# Micro.net
KiCad netlist of a schematic drawn in Altium Designer
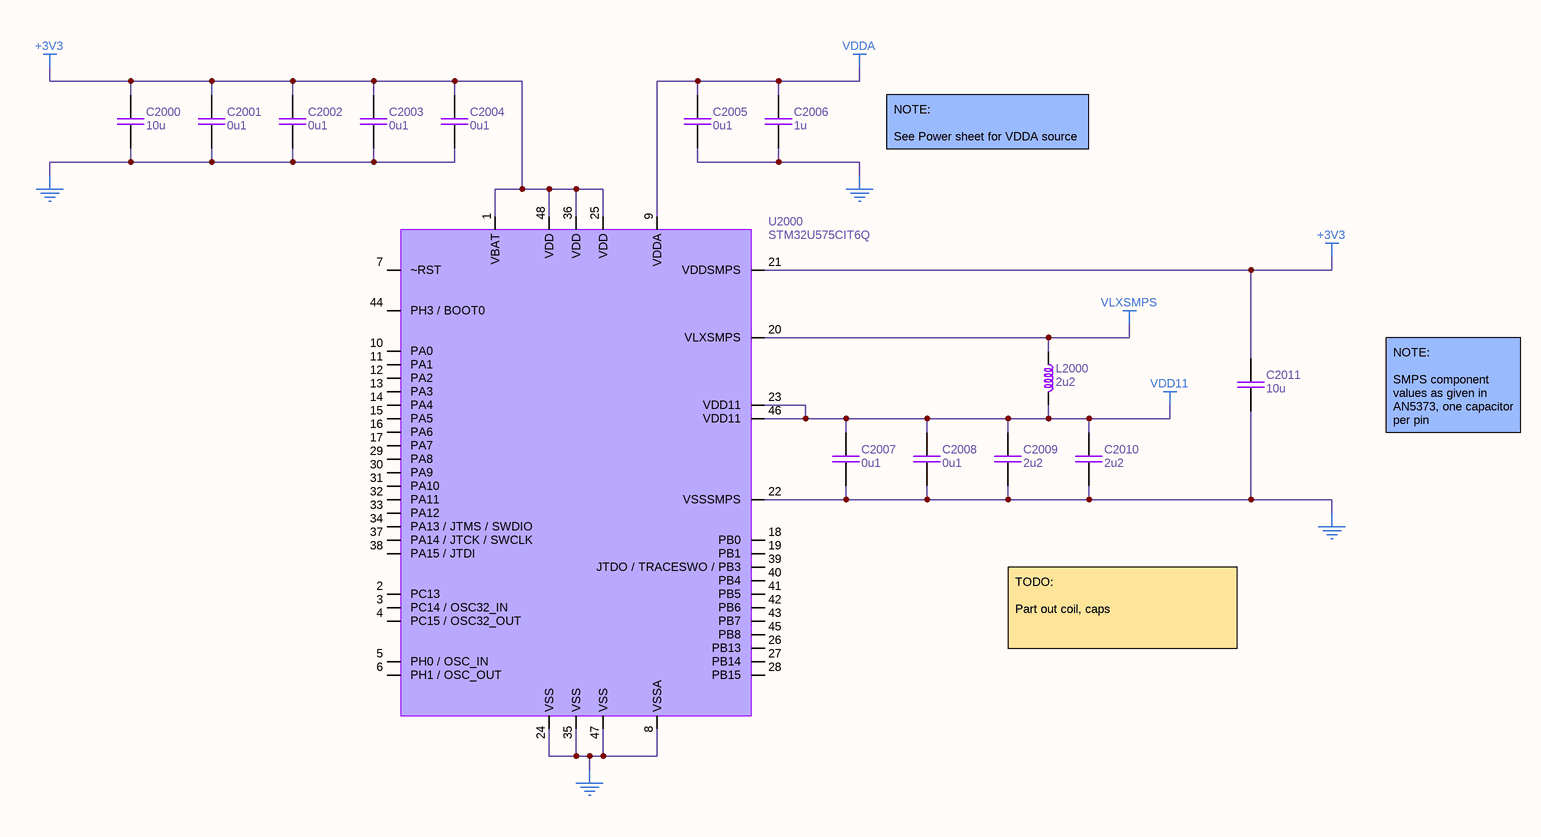
[diagram p0: Micro.SchDoc]

(export (version "E")
  (design (tool "Eeschema 10.0.6"))
  (components
    (comp (ref "C2000")
      (value "10u")
      (footprint "CC1206KKX7R8BB106_SMT_1206")
      (description "1206 SMT 10u 25V X7R ceramic capacitor")
      (fields
        (field (name "MANUFACTURER") "YAGEO")
        (field (name "MANUFACTURER PART NUMBER") "CC1206KKX7R8BB106")
      )
      (libsource (lib "algovision") (part "CC1206KKX7R8BB106_SMT_1206"))
    )
    (comp (ref "C2001")
      (value "0u1")
      (footprint "CC0402KRX7R7BB104_SMT_0402")
      (description "0402 SMT 0u1 16V X7R ceramic capacitor")
      (fields
        (field (name "MANUFACTURER") "YAGEO")
        (field (name "MANUFACTURER PART NUMBER") "CC0402KRX7R7BB104")
      )
      (libsource (lib "algovision") (part "CC0402KRX7R7BB104_SMT_0402"))
    )
    (comp (ref "C2002")
      (value "0u1")
      (footprint "CC0402KRX7R7BB104_SMT_0402")
      (description "0402 SMT 0u1 16V X7R ceramic capacitor")
      (fields
        (field (name "MANUFACTURER") "YAGEO")
        (field (name "MANUFACTURER PART NUMBER") "CC0402KRX7R7BB104")
      )
      (libsource (lib "algovision") (part "CC0402KRX7R7BB104_SMT_0402"))
    )
    (comp (ref "C2003")
      (value "0u1")
      (footprint "CC0402KRX7R7BB104_SMT_0402")
      (description "0402 SMT 0u1 16V X7R ceramic capacitor")
      (fields
        (field (name "MANUFACTURER") "YAGEO")
        (field (name "MANUFACTURER PART NUMBER") "CC0402KRX7R7BB104")
      )
      (libsource (lib "algovision") (part "CC0402KRX7R7BB104_SMT_0402"))
    )
    (comp (ref "C2004")
      (value "0u1")
      (footprint "CC0402KRX7R7BB104_SMT_0402")
      (description "0402 SMT 0u1 16V X7R ceramic capacitor")
      (fields
        (field (name "MANUFACTURER") "YAGEO")
        (field (name "MANUFACTURER PART NUMBER") "CC0402KRX7R7BB104")
      )
      (libsource (lib "algovision") (part "CC0402KRX7R7BB104_SMT_0402"))
    )
    (comp (ref "C2005")
      (value "0u1")
      (footprint "CC0402KRX7R7BB104_SMT_0402")
      (description "0402 SMT 0u1 16V X7R ceramic capacitor")
      (fields
        (field (name "MANUFACTURER") "YAGEO")
        (field (name "MANUFACTURER PART NUMBER") "CC0402KRX7R7BB104")
      )
      (libsource (lib "algovision") (part "CC0402KRX7R7BB104_SMT_0402"))
    )
    (comp (ref "C2006")
      (value "1u")
      (footprint "CC0603KRX7R7BB105_SMT_0603")
      (description "0603 SMT 1u 16V X7R ceramic capacitor")
      (fields
        (field (name "MANUFACTURER") "YAGEO")
        (field (name "MANUFACTURER PART NUMBER") "CC0603KRX7R7BB105")
      )
      (libsource (lib "algovision") (part "CC0603KRX7R7BB105_SMT_0603"))
    )
    (comp (ref "C2007")
      (value "0u1")
      (footprint "CC0402KRX7R7BB104_SMT_0402")
      (description "0402 SMT 0u1 16V X7R ceramic capacitor")
      (fields
        (field (name "MANUFACTURER") "YAGEO")
        (field (name "MANUFACTURER PART NUMBER") "CC0402KRX7R7BB104")
      )
      (libsource (lib "algovision") (part "CC0402KRX7R7BB104_SMT_0402"))
    )
    (comp (ref "C2008")
      (value "0u1")
      (footprint "CC0402KRX7R7BB104_SMT_0402")
      (description "0402 SMT 0u1 16V X7R ceramic capacitor")
      (fields
        (field (name "MANUFACTURER") "YAGEO")
        (field (name "MANUFACTURER PART NUMBER") "CC0402KRX7R7BB104")
      )
      (libsource (lib "algovision") (part "CC0402KRX7R7BB104_SMT_0402"))
    )
    (comp (ref "C2009")
      (value "2u2")
      (footprint "CC0402KRX7R7BB104_SMT_0402")
      (description "0402 SMT 0u1 16V X7R ceramic capacitor")
      (fields
        (field (name "MANUFACTURER") "YAGEO")
        (field (name "MANUFACTURER PART NUMBER") "CC0402KRX7R7BB104")
      )
      (libsource (lib "algovision") (part "CC0402KRX7R7BB104_SMT_0402"))
    )
    (comp (ref "C2010")
      (value "2u2")
      (footprint "CC0402KRX7R7BB104_SMT_0402")
      (description "0402 SMT 0u1 16V X7R ceramic capacitor")
      (fields
        (field (name "MANUFACTURER") "YAGEO")
        (field (name "MANUFACTURER PART NUMBER") "CC0402KRX7R7BB104")
      )
      (libsource (lib "algovision") (part "CC0402KRX7R7BB104_SMT_0402"))
    )
    (comp (ref "C2011")
      (value "10u")
      (footprint "CC1206KKX7R8BB106_SMT_1206")
      (description "1206 SMT 10u 25V X7R ceramic capacitor")
      (fields
        (field (name "MANUFACTURER") "YAGEO")
        (field (name "MANUFACTURER PART NUMBER") "CC1206KKX7R8BB106")
      )
      (libsource (lib "algovision") (part "CC1206KKX7R8BB106_SMT_1206"))
    )
    (comp (ref "L2000")
      (value "2u2")
      (description "TODO INDUCTOR")
      (libsource (lib "algovision") (part "INDUCTOR"))
    )
    (comp (ref "U2000")
      (value "STM32U575CIT6Q")
      (footprint "STM32U575CIT6Q_SMT_48-LQFP")
      (description "48-LQFP SMT STM32U5 32-bit ARM Cortex-M33 microcontroller")
      (fields (field (name "MANUFACTURER") "STMicroelectronics"))
      (libsource (lib "algovision") (part "STM32U575CIT6Q_SMT_48-LQFP"))
    )
  )
  (nets
    (net (code "1") (name "+3V3") (class "Default")
      (node (ref "C2000") (pin "2") (pinfunction "2_2") (pintype "passive"))
      (node (ref "C2001") (pin "2") (pinfunction "2_2") (pintype "passive"))
      (node (ref "C2002") (pin "2") (pinfunction "2_2") (pintype "passive"))
      (node (ref "C2003") (pin "2") (pinfunction "2_2") (pintype "passive"))
      (node (ref "C2004") (pin "2") (pinfunction "2_2") (pintype "passive"))
      (node (ref "C2011") (pin "2") (pinfunction "2_2") (pintype "passive"))
      (node (ref "U2000") (pin "1") (pinfunction "VBAT_1") (pintype "power_in"))
      (node (ref "U2000") (pin "21") (pinfunction "VDDSMPS_21") (pintype "power_in"))
      (node (ref "U2000") (pin "25") (pinfunction "VDD_25") (pintype "power_in"))
      (node (ref "U2000") (pin "36") (pinfunction "VDD_36") (pintype "power_in"))
      (node (ref "U2000") (pin "48") (pinfunction "VDD_48") (pintype "power_in"))
    )
    (net (code "2") (name "GND") (class "Default")
      (node (ref "C2000") (pin "1") (pinfunction "1_1") (pintype "passive"))
      (node (ref "C2001") (pin "1") (pinfunction "1_1") (pintype "passive"))
      (node (ref "C2002") (pin "1") (pinfunction "1_1") (pintype "passive"))
      (node (ref "C2003") (pin "1") (pinfunction "1_1") (pintype "passive"))
      (node (ref "C2004") (pin "1") (pinfunction "1_1") (pintype "passive"))
      (node (ref "C2005") (pin "1") (pinfunction "1_1") (pintype "passive"))
      (node (ref "C2006") (pin "1") (pinfunction "1_1") (pintype "passive"))
      (node (ref "C2007") (pin "1") (pinfunction "1_1") (pintype "passive"))
      (node (ref "C2008") (pin "1") (pinfunction "1_1") (pintype "passive"))
      (node (ref "C2009") (pin "1") (pinfunction "1_1") (pintype "passive"))
      (node (ref "C2010") (pin "1") (pinfunction "1_1") (pintype "passive"))
      (node (ref "C2011") (pin "1") (pinfunction "1_1") (pintype "passive"))
      (node (ref "U2000") (pin "22") (pinfunction "VSSSMPS_22") (pintype "power_in"))
      (node (ref "U2000") (pin "24") (pinfunction "VSS_24") (pintype "power_in"))
      (node (ref "U2000") (pin "35") (pinfunction "VSS_35") (pintype "power_in"))
      (node (ref "U2000") (pin "47") (pinfunction "VSS_47") (pintype "power_in"))
      (node (ref "U2000") (pin "8") (pinfunction "VSSA_8") (pintype "power_in"))
    )
    (net (code "3") (name "VDD11") (class "Default")
      (node (ref "C2007") (pin "2") (pinfunction "2_2") (pintype "passive"))
      (node (ref "C2008") (pin "2") (pinfunction "2_2") (pintype "passive"))
      (node (ref "C2009") (pin "2") (pinfunction "2_2") (pintype "passive"))
      (node (ref "C2010") (pin "2") (pinfunction "2_2") (pintype "passive"))
      (node (ref "L2000") (pin "2") (pinfunction "2_2") (pintype "passive"))
      (node (ref "U2000") (pin "23") (pinfunction "VDD11_23") (pintype "power_in"))
      (node (ref "U2000") (pin "46") (pinfunction "VDD11_46") (pintype "power_in"))
    )
    (net (code "4") (name "VDDA") (class "Default")
      (node (ref "C2005") (pin "2") (pinfunction "2_2") (pintype "passive"))
      (node (ref "C2006") (pin "2") (pinfunction "2_2") (pintype "passive"))
      (node (ref "U2000") (pin "9") (pinfunction "VDDA_9") (pintype "power_in"))
    )
    (net (code "5") (name "VLXSMPS") (class "Default")
      (node (ref "L2000") (pin "1") (pinfunction "1_1") (pintype "passive"))
      (node (ref "U2000") (pin "20") (pinfunction "VLXSMPS_20") (pintype "power_in"))
    )
    (net (code "6") (name "unconnected-(U2000-JTDO_{slash}_TRACESWO_{slash}_PB3-Pad39)") (class "Default")
      (node (ref "U2000") (pin "39") (pinfunction "JTDO_/_TRACESWO_/_PB3_39") (pintype "bidirectional"))
    )
    (net (code "7") (name "unconnected-(U2000-PA0-Pad10)") (class "Default")
      (node (ref "U2000") (pin "10") (pinfunction "PA0_10") (pintype "bidirectional"))
    )
    (net (code "8") (name "unconnected-(U2000-PA1-Pad11)") (class "Default")
      (node (ref "U2000") (pin "11") (pinfunction "PA1_11") (pintype "bidirectional"))
    )
    (net (code "9") (name "unconnected-(U2000-PA2-Pad12)") (class "Default")
      (node (ref "U2000") (pin "12") (pinfunction "PA2_12") (pintype "bidirectional"))
    )
    (net (code "10") (name "unconnected-(U2000-PA3-Pad13)") (class "Default")
      (node (ref "U2000") (pin "13") (pinfunction "PA3_13") (pintype "bidirectional"))
    )
    (net (code "11") (name "unconnected-(U2000-PA4-Pad14)") (class "Default")
      (node (ref "U2000") (pin "14") (pinfunction "PA4_14") (pintype "bidirectional"))
    )
    (net (code "12") (name "unconnected-(U2000-PA5-Pad15)") (class "Default")
      (node (ref "U2000") (pin "15") (pinfunction "PA5_15") (pintype "bidirectional"))
    )
    (net (code "13") (name "unconnected-(U2000-PA6-Pad16)") (class "Default")
      (node (ref "U2000") (pin "16") (pinfunction "PA6_16") (pintype "bidirectional"))
    )
    (net (code "14") (name "unconnected-(U2000-PA7-Pad17)") (class "Default")
      (node (ref "U2000") (pin "17") (pinfunction "PA7_17") (pintype "bidirectional"))
    )
    (net (code "15") (name "unconnected-(U2000-PA8-Pad29)") (class "Default")
      (node (ref "U2000") (pin "29") (pinfunction "PA8_29") (pintype "bidirectional"))
    )
    (net (code "16") (name "unconnected-(U2000-PA9-Pad30)") (class "Default")
      (node (ref "U2000") (pin "30") (pinfunction "PA9_30") (pintype "bidirectional"))
    )
    (net (code "17") (name "unconnected-(U2000-PA10-Pad31)") (class "Default")
      (node (ref "U2000") (pin "31") (pinfunction "PA10_31") (pintype "bidirectional"))
    )
    (net (code "18") (name "unconnected-(U2000-PA11-Pad32)") (class "Default")
      (node (ref "U2000") (pin "32") (pinfunction "PA11_32") (pintype "bidirectional"))
    )
    (net (code "19") (name "unconnected-(U2000-PA12-Pad33)") (class "Default")
      (node (ref "U2000") (pin "33") (pinfunction "PA12_33") (pintype "bidirectional"))
    )
    (net (code "20") (name "unconnected-(U2000-PA13_{slash}_JTMS_{slash}_SWDIO-Pad34)") (class "Default")
      (node (ref "U2000") (pin "34") (pinfunction "PA13_/_JTMS_/_SWDIO_34") (pintype "bidirectional"))
    )
    (net (code "21") (name "unconnected-(U2000-PA14_{slash}_JTCK_{slash}_SWCLK-Pad37)") (class "Default")
      (node (ref "U2000") (pin "37") (pinfunction "PA14_/_JTCK_/_SWCLK_37") (pintype "bidirectional"))
    )
    (net (code "22") (name "unconnected-(U2000-PA15_{slash}_JTDI-Pad38)") (class "Default")
      (node (ref "U2000") (pin "38") (pinfunction "PA15_/_JTDI_38") (pintype "bidirectional"))
    )
    (net (code "23") (name "unconnected-(U2000-PB0-Pad18)") (class "Default")
      (node (ref "U2000") (pin "18") (pinfunction "PB0_18") (pintype "bidirectional"))
    )
    (net (code "24") (name "unconnected-(U2000-PB1-Pad19)") (class "Default")
      (node (ref "U2000") (pin "19") (pinfunction "PB1_19") (pintype "bidirectional"))
    )
    (net (code "25") (name "unconnected-(U2000-PB4-Pad40)") (class "Default")
      (node (ref "U2000") (pin "40") (pinfunction "PB4_40") (pintype "bidirectional"))
    )
    (net (code "26") (name "unconnected-(U2000-PB5-Pad41)") (class "Default")
      (node (ref "U2000") (pin "41") (pinfunction "PB5_41") (pintype "bidirectional"))
    )
    (net (code "27") (name "unconnected-(U2000-PB6-Pad42)") (class "Default")
      (node (ref "U2000") (pin "42") (pinfunction "PB6_42") (pintype "bidirectional"))
    )
    (net (code "28") (name "unconnected-(U2000-PB7-Pad43)") (class "Default")
      (node (ref "U2000") (pin "43") (pinfunction "PB7_43") (pintype "bidirectional"))
    )
    (net (code "29") (name "unconnected-(U2000-PB8-Pad45)") (class "Default")
      (node (ref "U2000") (pin "45") (pinfunction "PB8_45") (pintype "bidirectional"))
    )
    (net (code "30") (name "unconnected-(U2000-PB13-Pad26)") (class "Default")
      (node (ref "U2000") (pin "26") (pinfunction "PB13_26") (pintype "bidirectional"))
    )
    (net (code "31") (name "unconnected-(U2000-PB14-Pad27)") (class "Default")
      (node (ref "U2000") (pin "27") (pinfunction "PB14_27") (pintype "bidirectional"))
    )
    (net (code "32") (name "unconnected-(U2000-PB15-Pad28)") (class "Default")
      (node (ref "U2000") (pin "28") (pinfunction "PB15_28") (pintype "bidirectional"))
    )
    (net (code "33") (name "unconnected-(U2000-PC13-Pad2)") (class "Default")
      (node (ref "U2000") (pin "2") (pinfunction "PC13_2") (pintype "bidirectional"))
    )
    (net (code "34") (name "unconnected-(U2000-PC14_{slash}_OSC32_IN-Pad3)") (class "Default")
      (node (ref "U2000") (pin "3") (pinfunction "PC14_/_OSC32_IN_3") (pintype "bidirectional"))
    )
    (net (code "35") (name "unconnected-(U2000-PC15_{slash}_OSC32_OUT-Pad4)") (class "Default")
      (node (ref "U2000") (pin "4") (pinfunction "PC15_/_OSC32_OUT_4") (pintype "bidirectional"))
    )
    (net (code "36") (name "unconnected-(U2000-PH0_{slash}_OSC_IN-Pad5)") (class "Default")
      (node (ref "U2000") (pin "5") (pinfunction "PH0_/_OSC_IN_5") (pintype "bidirectional"))
    )
    (net (code "37") (name "unconnected-(U2000-PH1_{slash}_OSC_OUT-Pad6)") (class "Default")
      (node (ref "U2000") (pin "6") (pinfunction "PH1_/_OSC_OUT_6") (pintype "bidirectional"))
    )
    (net (code "38") (name "unconnected-(U2000-PH3_{slash}_BOOT0-Pad44)") (class "Default")
      (node (ref "U2000") (pin "44") (pinfunction "PH3_/_BOOT0_44") (pintype "bidirectional"))
    )
    (net (code "39") (name "unconnected-(U2000-~RST-Pad7)") (class "Default")
      (node (ref "U2000") (pin "7") (pinfunction "~RST_7") (pintype "bidirectional"))
    )
  )
)
